# smart-timed-plug.net
KiCad netlist of a schematic drawn in EAGLE
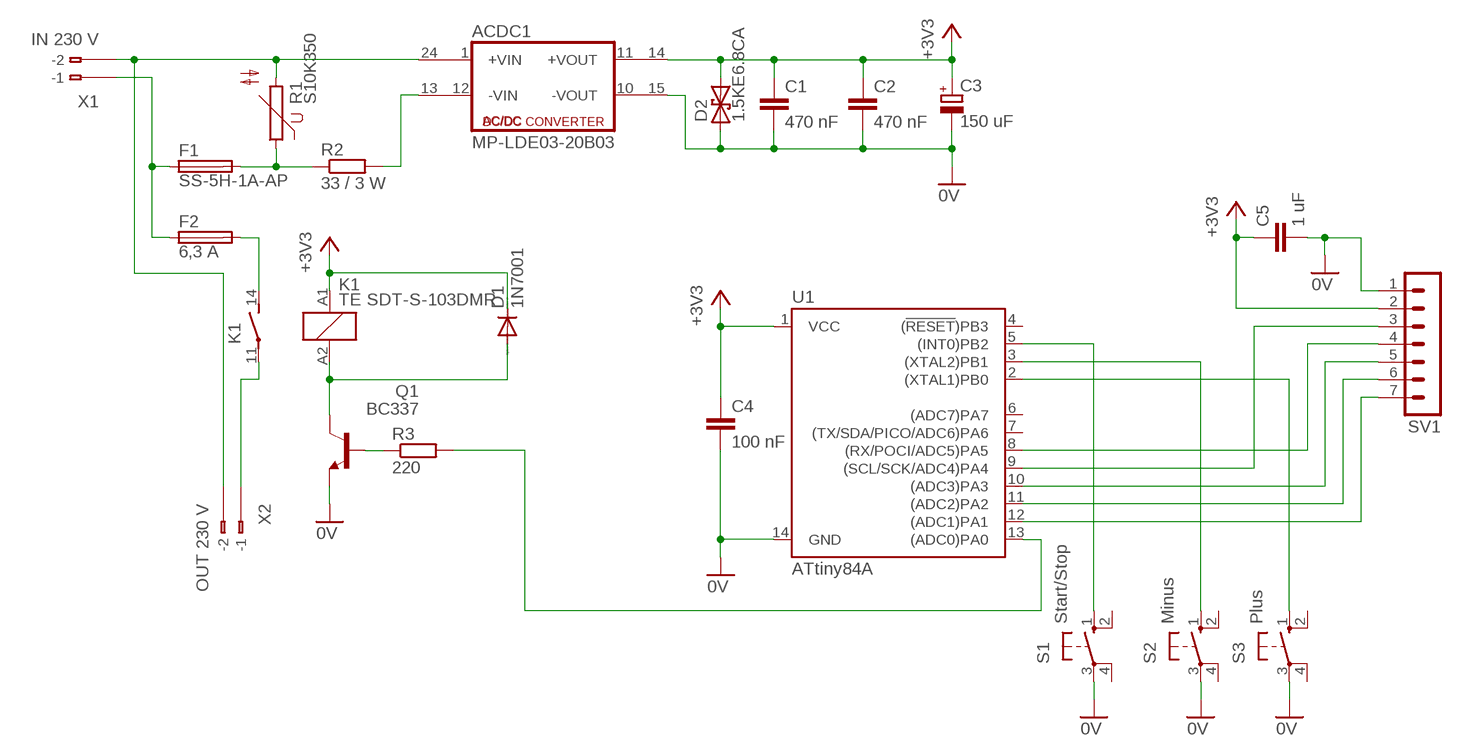
[diagram p0: schematic, sheet 1]

(export (version "E")
  (design (tool "Eeschema 10.0.6"))
  (components
    (comp (ref "ACDC1")
      (value "MP-LDE03-20B03")
      (footprint "eagle-import:CMK")
      (libsource (lib "eagle-import") (part "DC213R"))
    )
    (comp (ref "C1")
      (value "470 nF")
      (footprint "eagle-import:C025-050X050")
      (libsource (lib "eagle-import") (part "C-EU025-050X050"))
    )
    (comp (ref "C2")
      (value "470 nF")
      (footprint "eagle-import:C025-050X050")
      (libsource (lib "eagle-import") (part "C-EU025-050X050"))
    )
    (comp (ref "C3")
      (value "150 uF")
      (footprint "eagle-import:E2,5-5")
      (libsource (lib "eagle-import") (part "CPOL-EUE2.5-5"))
    )
    (comp (ref "C4")
      (value "100 nF")
      (footprint "eagle-import:C025-050X050")
      (libsource (lib "eagle-import") (part "C-EU025-050X050"))
    )
    (comp (ref "C5")
      (value "1 uF")
      (footprint "eagle-import:C025-050X050")
      (libsource (lib "eagle-import") (part "C-EU025-050X050"))
    )
    (comp (ref "D1")
      (value "1N7001")
      (footprint "eagle-import:DO201-15")
      (libsource (lib "eagle-import") (part "1N5624"))
    )
    (comp (ref "D2")
      (value "1.5KE6.8CA")
      (footprint "eagle-import:F126Z12")
      (libsource (lib "eagle-import") (part "BZW04XXB"))
    )
    (comp (ref "F1")
      (value "SS-5H-1A-AP")
      (footprint "eagle-import:GSH15")
      (fields (field (name "MPN") "64900001039"))
      (libsource (lib "eagle-import") (part "GSH15"))
    )
    (comp (ref "F2")
      (value "6,3 A")
      (footprint "eagle-import:GSH15")
      (fields (field (name "MPN") "64900001039"))
      (libsource (lib "eagle-import") (part "GSH15"))
    )
    (comp (ref "K1")
      (value "TE SDT-S-103DMR")
      (footprint "eagle-import:RT-N_O12A5")
      (fields (field (name "MF") "TYCO ELECTRONICS") (field (name "MPN") "4-1393231-5"))
      (libsource (lib "eagle-import") (part "RP?314012"))
    )
    (comp (ref "Q1")
      (value "BC337")
      (footprint "eagle-import:TO92")
      (libsource (lib "eagle-import") (part "BC337"))
    )
    (comp (ref "R1")
      (value "S10K350")
      (footprint "eagle-import:S10K320")
      (libsource (lib "eagle-import") (part "S10K320"))
    )
    (comp (ref "R2")
      (value "33 / 3 W")
      (footprint "eagle-import:0207_10")
      (libsource (lib "eagle-import") (part "R-EU_0207/10"))
    )
    (comp (ref "R3")
      (value "220")
      (footprint "eagle-import:0207_10")
      (libsource (lib "eagle-import") (part "R-EU_0207/10"))
    )
    (comp (ref "S1")
      (value "Start/Stop")
      (footprint "eagle-import:B3F-10XX")
      (fields (field (name "MPN") "B3F-1000"))
      (libsource (lib "eagle-import") (part "10-XX"))
    )
    (comp (ref "S2")
      (value "Minus")
      (footprint "eagle-import:B3F-10XX")
      (fields (field (name "MPN") "B3F-1000"))
      (libsource (lib "eagle-import") (part "10-XX"))
    )
    (comp (ref "S3")
      (value "Plus")
      (footprint "eagle-import:B3F-10XX")
      (fields (field (name "MPN") "B3F-1000"))
      (libsource (lib "eagle-import") (part "10-XX"))
    )
    (comp (ref "SV1")
      (value "MA07-1")
      (footprint "eagle-import:MA07-1")
      (libsource (lib "eagle-import") (part "MA07-1"))
    )
    (comp (ref "U1")
      (value "ATtiny84A")
      (footprint "eagle-import:DIP14")
      (libsource (lib "eagle-import") (part "ATTINY84ATTINY84-20PU"))
    )
    (comp (ref "X1")
      (value "IN 230 V")
      (footprint "eagle-import:233-102")
      (fields (field (name "MPN") "233-102"))
      (libsource (lib "eagle-import") (part "233-102"))
    )
    (comp (ref "X2")
      (value "OUT 230 V")
      (footprint "eagle-import:233-102")
      (fields (field (name "MPN") "233-102"))
      (libsource (lib "eagle-import") (part "233-102"))
    )
  )
  (nets
    (net (code "1") (name "+3V3") (class "Default")
      (node (ref "ACDC1") (pin "14") (pinfunction "+VOUT1_14") (pintype "passive"))
      (node (ref "C1") (pin "1") (pinfunction "1_1") (pintype "passive"))
      (node (ref "C2") (pin "1") (pinfunction "1_1") (pintype "passive"))
      (node (ref "C3") (pin "+") (pinfunction "+_+") (pintype "passive"))
      (node (ref "C4") (pin "1") (pinfunction "1_1") (pintype "passive"))
      (node (ref "C5") (pin "1") (pinfunction "1_1") (pintype "passive"))
      (node (ref "D1") (pin "C") (pinfunction "C_C") (pintype "passive"))
      (node (ref "D2") (pin "C") (pinfunction "2_C") (pintype "passive"))
      (node (ref "K1") (pin "A1") (pinfunction "1_A1") (pintype "passive"))
      (node (ref "SV1") (pin "2") (pinfunction "2_2") (pintype "passive"))
      (node (ref "U1") (pin "1") (pinfunction "VCC_1") (pintype "bidirectional"))
    )
    (net (code "2") (name "0V") (class "Default")
      (node (ref "ACDC1") (pin "15") (pinfunction "-VOUT1_15") (pintype "passive"))
      (node (ref "C1") (pin "2") (pinfunction "2_2") (pintype "passive"))
      (node (ref "C2") (pin "2") (pinfunction "2_2") (pintype "passive"))
      (node (ref "C3") (pin "-") (pinfunction "-_-") (pintype "passive"))
      (node (ref "C4") (pin "2") (pinfunction "2_2") (pintype "passive"))
      (node (ref "C5") (pin "2") (pinfunction "2_2") (pintype "passive"))
      (node (ref "D2") (pin "A") (pinfunction "1_A") (pintype "passive"))
      (node (ref "Q1") (pin "1") (pinfunction "E_1") (pintype "passive"))
      (node (ref "S1") (pin "3") (pinfunction "P_3") (pintype "passive"))
      (node (ref "S2") (pin "3") (pinfunction "P_3") (pintype "passive"))
      (node (ref "S3") (pin "3") (pinfunction "P_3") (pintype "passive"))
      (node (ref "SV1") (pin "1") (pinfunction "1_1") (pintype "passive"))
      (node (ref "U1") (pin "14") (pinfunction "GND_14") (pintype "bidirectional"))
    )
    (net (code "3") (name "Net-(ACDC1-+VIN1)") (class "Default")
      (node (ref "ACDC1") (pin "24") (pinfunction "+VIN1_24") (pintype "passive"))
      (node (ref "R1") (pin "2") (pinfunction "2_2") (pintype "passive"))
      (node (ref "X1") (pin "B2") (pinfunction "B-2_B2") (pintype "passive"))
      (node (ref "X2") (pin "B2") (pinfunction "B-2_B2") (pintype "passive"))
    )
    (net (code "4") (name "Net-(ACDC1--VIN1)") (class "Default")
      (node (ref "ACDC1") (pin "13") (pinfunction "-VIN1_13") (pintype "passive"))
      (node (ref "R2") (pin "2") (pinfunction "2_2") (pintype "passive"))
    )
    (net (code "5") (name "Net-(F1-Pad2)") (class "Default")
      (node (ref "F1") (pin "2") (pinfunction "2_2") (pintype "passive"))
      (node (ref "R1") (pin "1") (pinfunction "1_1") (pintype "passive"))
      (node (ref "R2") (pin "1") (pinfunction "1_1") (pintype "passive"))
    )
    (net (code "6") (name "Net-(K1A-2)") (class "Default")
      (node (ref "D1") (pin "A") (pinfunction "A_A") (pintype "passive"))
      (node (ref "K1") (pin "A2") (pinfunction "2_A2") (pintype "passive"))
      (node (ref "Q1") (pin "3") (pinfunction "C_3") (pintype "passive"))
    )
    (net (code "7") (name "Net-(K1B-P)") (class "Default")
      (node (ref "K1") (pin "11") (pinfunction "P_11") (pintype "passive"))
      (node (ref "X2") (pin "B1") (pinfunction "B-1_B1") (pintype "passive"))
    )
    (net (code "8") (name "Net-(K1B-S)") (class "Default")
      (node (ref "F2") (pin "2") (pinfunction "2_2") (pintype "passive"))
      (node (ref "K1") (pin "14") (pinfunction "S_14") (pintype "passive"))
    )
    (net (code "9") (name "Net-(Q1-B)") (class "Default")
      (node (ref "Q1") (pin "2") (pinfunction "B_2") (pintype "passive"))
      (node (ref "R3") (pin "1") (pinfunction "1_1") (pintype "passive"))
    )
    (net (code "10") (name "Net-(S1-S)") (class "Default")
      (node (ref "S1") (pin "1") (pinfunction "S_1") (pintype "passive"))
      (node (ref "U1") (pin "5") (pinfunction "(INT0)PB2_5") (pintype "bidirectional"))
    )
    (net (code "11") (name "Net-(S2-S)") (class "Default")
      (node (ref "S2") (pin "1") (pinfunction "S_1") (pintype "passive"))
      (node (ref "U1") (pin "3") (pinfunction "(XTAL2)PB1_3") (pintype "bidirectional"))
    )
    (net (code "12") (name "Net-(S3-S)") (class "Default")
      (node (ref "S3") (pin "1") (pinfunction "S_1") (pintype "passive"))
      (node (ref "U1") (pin "2") (pinfunction "(XTAL1)PB0_2") (pintype "bidirectional"))
    )
    (net (code "13") (name "Net-(U1-(ADC0)PA0)") (class "Default")
      (node (ref "R3") (pin "2") (pinfunction "2_2") (pintype "passive"))
      (node (ref "U1") (pin "13") (pinfunction "(ADC0)PA0_13") (pintype "bidirectional"))
    )
    (net (code "14") (name "Net-(U1-(ADC1)PA1)") (class "Default")
      (node (ref "SV1") (pin "7") (pinfunction "7_7") (pintype "passive"))
      (node (ref "U1") (pin "12") (pinfunction "(ADC1)PA1_12") (pintype "bidirectional"))
    )
    (net (code "15") (name "Net-(U1-(ADC2)PA2)") (class "Default")
      (node (ref "SV1") (pin "6") (pinfunction "6_6") (pintype "passive"))
      (node (ref "U1") (pin "11") (pinfunction "(ADC2)PA2_11") (pintype "bidirectional"))
    )
    (net (code "16") (name "Net-(U1-(ADC3)PA3)") (class "Default")
      (node (ref "SV1") (pin "5") (pinfunction "5_5") (pintype "passive"))
      (node (ref "U1") (pin "10") (pinfunction "(ADC3)PA3_10") (pintype "bidirectional"))
    )
    (net (code "17") (name "Net-(U1-(RX{slash}POCI{slash}ADC5)PA5)") (class "Default")
      (node (ref "SV1") (pin "4") (pinfunction "4_4") (pintype "passive"))
      (node (ref "U1") (pin "8") (pinfunction "(RX/POCI/ADC5)PA5_8") (pintype "bidirectional"))
    )
    (net (code "18") (name "Net-(U1-(SCL{slash}SCK{slash}ADC4)PA4)") (class "Default")
      (node (ref "SV1") (pin "3") (pinfunction "3_3") (pintype "passive"))
      (node (ref "U1") (pin "9") (pinfunction "(SCL/SCK/ADC4)PA4_9") (pintype "bidirectional"))
    )
    (net (code "19") (name "Net-(X1-B-1)") (class "Default")
      (node (ref "F1") (pin "1") (pinfunction "1_1") (pintype "passive"))
      (node (ref "F2") (pin "1") (pinfunction "1_1") (pintype "passive"))
      (node (ref "X1") (pin "B1") (pinfunction "B-1_B1") (pintype "passive"))
    )
    (net (code "20") (name "unconnected-(ACDC1-+VIN-Pad1)") (class "Default")
      (node (ref "ACDC1") (pin "1") (pinfunction "+VIN_1") (pintype "passive"))
    )
    (net (code "21") (name "unconnected-(ACDC1-+VOUT-Pad11)") (class "Default")
      (node (ref "ACDC1") (pin "11") (pinfunction "+VOUT_11") (pintype "passive"))
    )
    (net (code "22") (name "unconnected-(ACDC1--VIN-Pad12)") (class "Default")
      (node (ref "ACDC1") (pin "12") (pinfunction "-VIN_12") (pintype "passive"))
    )
    (net (code "23") (name "unconnected-(ACDC1--VOUT-Pad10)") (class "Default")
      (node (ref "ACDC1") (pin "10") (pinfunction "-VOUT_10") (pintype "passive"))
    )
    (net (code "24") (name "unconnected-(S1-P1-Pad4)") (class "Default")
      (node (ref "S1") (pin "4") (pinfunction "P1_4") (pintype "passive"))
    )
    (net (code "25") (name "unconnected-(S1-S1-Pad2)") (class "Default")
      (node (ref "S1") (pin "2") (pinfunction "S1_2") (pintype "passive"))
    )
    (net (code "26") (name "unconnected-(S2-P1-Pad4)") (class "Default")
      (node (ref "S2") (pin "4") (pinfunction "P1_4") (pintype "passive"))
    )
    (net (code "27") (name "unconnected-(S2-S1-Pad2)") (class "Default")
      (node (ref "S2") (pin "2") (pinfunction "S1_2") (pintype "passive"))
    )
    (net (code "28") (name "unconnected-(S3-P1-Pad4)") (class "Default")
      (node (ref "S3") (pin "4") (pinfunction "P1_4") (pintype "passive"))
    )
    (net (code "29") (name "unconnected-(S3-S1-Pad2)") (class "Default")
      (node (ref "S3") (pin "2") (pinfunction "S1_2") (pintype "passive"))
    )
    (net (code "30") (name "unconnected-(U1-(ADC7)PA7-Pad6)") (class "Default")
      (node (ref "U1") (pin "6") (pinfunction "(ADC7)PA7_6") (pintype "bidirectional"))
    )
    (net (code "31") (name "unconnected-(U1-(TX{slash}SDA{slash}PICO{slash}ADC6)PA6-Pad7)") (class "Default")
      (node (ref "U1") (pin "7") (pinfunction "(TX/SDA/PICO/ADC6)PA6_7") (pintype "bidirectional"))
    )
    (net (code "32") (name "unconnected-(U1-(~{RESET})PB3-Pad4)") (class "Default")
      (node (ref "U1") (pin "4") (pinfunction "(~{RESET})PB3_4") (pintype "bidirectional"))
    )
    (net (code "33") (name "unconnected-(X1--1-PadA1)") (class "Default")
      (node (ref "X1") (pin "A1") (pinfunction "-1_A1") (pintype "passive"))
    )
    (net (code "34") (name "unconnected-(X1--2-PadA2)") (class "Default")
      (node (ref "X1") (pin "A2") (pinfunction "-2_A2") (pintype "passive"))
    )
    (net (code "35") (name "unconnected-(X2--1-PadA1)") (class "Default")
      (node (ref "X2") (pin "A1") (pinfunction "-1_A1") (pintype "passive"))
    )
    (net (code "36") (name "unconnected-(X2--2-PadA2)") (class "Default")
      (node (ref "X2") (pin "A2") (pinfunction "-2_A2") (pintype "passive"))
    )
  )
)
